# wifi.net
KiCad netlist of a schematic drawn in EAGLE
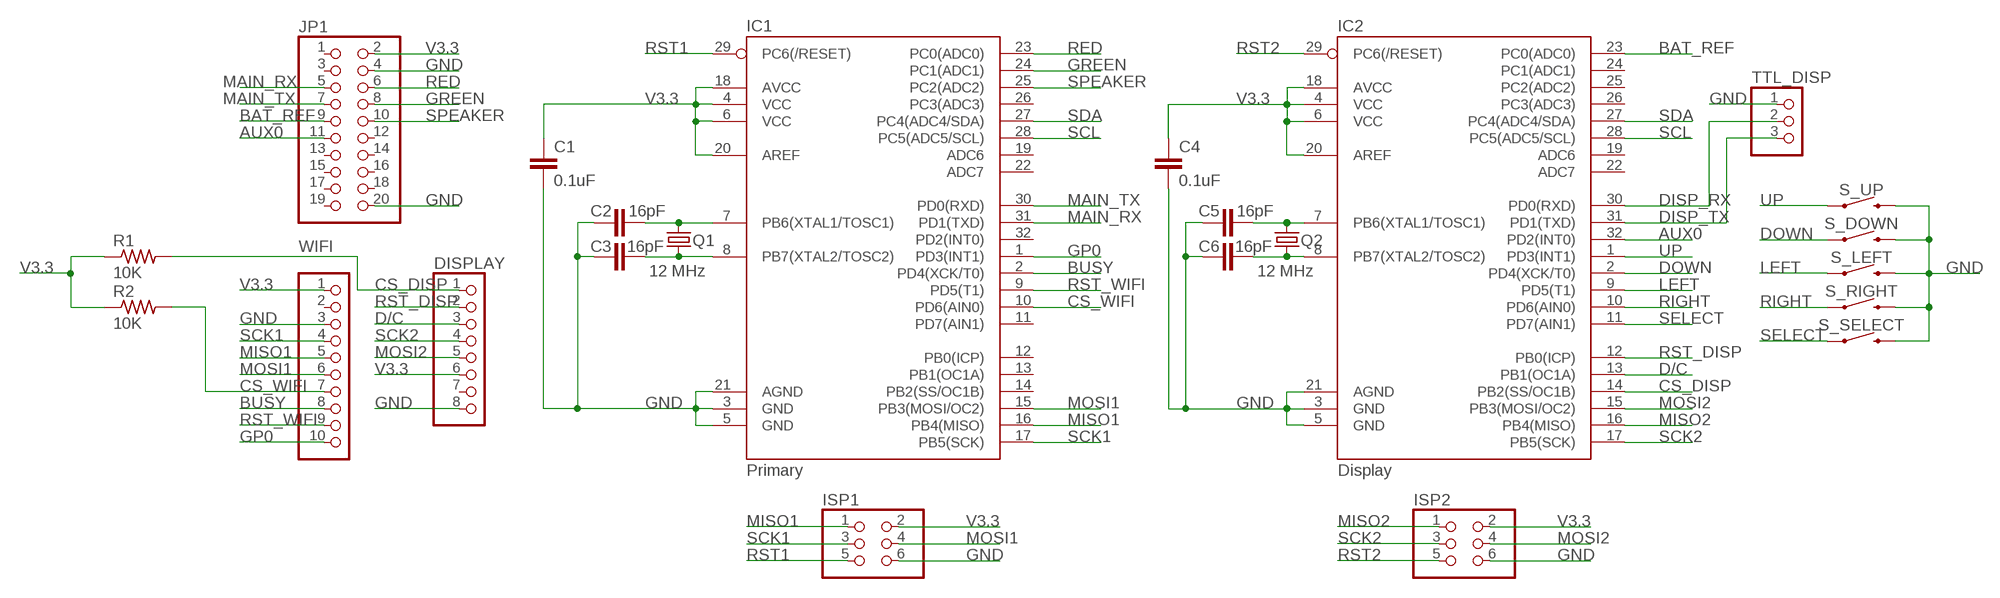
[diagram p0: schematic, sheet 1]

(export (version "E")
  (design (tool "Eeschema 10.0.6"))
  (components
    (comp (ref "C1")
      (value "0.1uF")
      (footprint "eagle-import:C1206")
      (libsource (lib "eagle-import") (part "C-EUC1206"))
    )
    (comp (ref "C2")
      (value "16pF")
      (footprint "eagle-import:C1206")
      (libsource (lib "eagle-import") (part "C-EUC1206"))
    )
    (comp (ref "C3")
      (value "16pF")
      (footprint "eagle-import:C1206")
      (libsource (lib "eagle-import") (part "C-EUC1206"))
    )
    (comp (ref "C4")
      (value "0.1uF")
      (footprint "eagle-import:C1206")
      (libsource (lib "eagle-import") (part "C-EUC1206"))
    )
    (comp (ref "C5")
      (value "16pF")
      (footprint "eagle-import:C1206")
      (libsource (lib "eagle-import") (part "C-EUC1206"))
    )
    (comp (ref "C6")
      (value "16pF")
      (footprint "eagle-import:C1206")
      (libsource (lib "eagle-import") (part "C-EUC1206"))
    )
    (comp (ref "DISPLAY")
      (value "PINHD-1X8CLEANBIG")
      (footprint "eagle-import:1X08-CLEANBIG")
      (libsource (lib "eagle-import") (part "PINHD-1X8CLEANBIG"))
    )
    (comp (ref "IC1")
      (value "Primary")
      (footprint "eagle-import:TQFP32-08")
      (libsource (lib "eagle-import") (part "ATMEGA328P_TQFP"))
    )
    (comp (ref "IC2")
      (value "Display")
      (footprint "eagle-import:TQFP32-08")
      (libsource (lib "eagle-import") (part "ATMEGA328P_TQFP"))
    )
    (comp (ref "ISP1")
      (value "PINHD-2X3")
      (footprint "eagle-import:2X03")
      (libsource (lib "eagle-import") (part "PINHD-2X3"))
    )
    (comp (ref "ISP2")
      (value "PINHD-2X3")
      (footprint "eagle-import:2X03")
      (libsource (lib "eagle-import") (part "PINHD-2X3"))
    )
    (comp (ref "JP1")
      (value "PINHD-2X10")
      (footprint "eagle-import:2X10")
      (libsource (lib "eagle-import") (part "PINHD-2X10"))
    )
    (comp (ref "Q1")
      (value "12 MHz")
      (footprint "eagle-import:HC49_S")
      (libsource (lib "eagle-import") (part "CRYSTALHC49S"))
    )
    (comp (ref "Q2")
      (value "12 MHz")
      (footprint "eagle-import:HC49_S")
      (libsource (lib "eagle-import") (part "CRYSTALHC49S"))
    )
    (comp (ref "R1")
      (value "10K")
      (footprint "eagle-import:R1206")
      (libsource (lib "eagle-import") (part "R-US_R1206"))
    )
    (comp (ref "R2")
      (value "10K")
      (footprint "eagle-import:R1206")
      (libsource (lib "eagle-import") (part "R-US_R1206"))
    )
    (comp (ref "S_DOWN")
      (value "MOMENTARY-SWITCH-SPST-PTH-6.0MM")
      (footprint "eagle-import:TACTILE_SWITCH_PTH_6.0MM")
      (libsource (lib "eagle-import") (part "MOMENTARY-SWITCH-SPST-PTH-6.0MM"))
    )
    (comp (ref "S_LEFT")
      (value "MOMENTARY-SWITCH-SPST-PTH-6.0MM")
      (footprint "eagle-import:TACTILE_SWITCH_PTH_6.0MM")
      (libsource (lib "eagle-import") (part "MOMENTARY-SWITCH-SPST-PTH-6.0MM"))
    )
    (comp (ref "S_RIGHT")
      (value "MOMENTARY-SWITCH-SPST-PTH-6.0MM")
      (footprint "eagle-import:TACTILE_SWITCH_PTH_6.0MM")
      (libsource (lib "eagle-import") (part "MOMENTARY-SWITCH-SPST-PTH-6.0MM"))
    )
    (comp (ref "S_SELECT")
      (value "MOMENTARY-SWITCH-SPST-PTH-6.0MM")
      (footprint "eagle-import:TACTILE_SWITCH_PTH_6.0MM")
      (libsource (lib "eagle-import") (part "MOMENTARY-SWITCH-SPST-PTH-6.0MM"))
    )
    (comp (ref "S_UP")
      (value "MOMENTARY-SWITCH-SPST-PTH-6.0MM")
      (footprint "eagle-import:TACTILE_SWITCH_PTH_6.0MM")
      (libsource (lib "eagle-import") (part "MOMENTARY-SWITCH-SPST-PTH-6.0MM"))
    )
    (comp (ref "TTL_DISP")
      (value "PINHD-1X3")
      (footprint "eagle-import:1X03")
      (libsource (lib "eagle-import") (part "PINHD-1X3"))
    )
    (comp (ref "WIFI")
      (value "PINHD-1X10")
      (footprint "eagle-import:1X10-BIG")
      (libsource (lib "eagle-import") (part "PINHD-1X10"))
    )
  )
  (nets
    (net (code "1") (name "/AUX0") (class "Default")
      (node (ref "IC2") (pin "32") (pinfunction "PD2(INT0)_32") (pintype "bidirectional"))
      (node (ref "JP1") (pin "11") (pinfunction "11_11") (pintype "passive"))
    )
    (net (code "2") (name "/BAT_REF") (class "Default")
      (node (ref "IC2") (pin "23") (pinfunction "PC0(ADC0)_23") (pintype "bidirectional"))
      (node (ref "JP1") (pin "9") (pinfunction "9_9") (pintype "passive"))
    )
    (net (code "3") (name "/BUSY") (class "Default")
      (node (ref "IC1") (pin "2") (pinfunction "PD4(XCK/T0)_2") (pintype "bidirectional"))
      (node (ref "WIFI") (pin "8") (pinfunction "8_8") (pintype "passive"))
    )
    (net (code "4") (name "/CS_DISP") (class "Default")
      (node (ref "DISPLAY") (pin "1") (pinfunction "1_1") (pintype "passive"))
      (node (ref "IC2") (pin "14") (pinfunction "PB2(SS/OC1B)_14") (pintype "bidirectional"))
      (node (ref "R1") (pin "2") (pinfunction "2_2") (pintype "passive"))
    )
    (net (code "5") (name "/CS_WIFI") (class "Default")
      (node (ref "IC1") (pin "10") (pinfunction "PD6(AIN0)_10") (pintype "bidirectional"))
      (node (ref "R2") (pin "2") (pinfunction "2_2") (pintype "passive"))
      (node (ref "WIFI") (pin "7") (pinfunction "7_7") (pintype "passive"))
    )
    (net (code "6") (name "/DISP_RX") (class "Default")
      (node (ref "IC2") (pin "30") (pinfunction "PD0(RXD)_30") (pintype "bidirectional"))
      (node (ref "TTL_DISP") (pin "2") (pinfunction "2_2") (pintype "passive"))
    )
    (net (code "7") (name "/DISP_TX") (class "Default")
      (node (ref "IC2") (pin "31") (pinfunction "PD1(TXD)_31") (pintype "bidirectional"))
      (node (ref "TTL_DISP") (pin "3") (pinfunction "3_3") (pintype "passive"))
    )
    (net (code "8") (name "/DOWN") (class "Default")
      (node (ref "IC2") (pin "2") (pinfunction "PD4(XCK/T0)_2") (pintype "bidirectional"))
      (node (ref "S_DOWN") (pin "1") (pinfunction "1_1") (pintype "passive"))
    )
    (net (code "9") (name "/D{slash}C") (class "Default")
      (node (ref "DISPLAY") (pin "3") (pinfunction "3_3") (pintype "passive"))
      (node (ref "IC2") (pin "13") (pinfunction "PB1(OC1A)_13") (pintype "bidirectional"))
    )
    (net (code "10") (name "/GND") (class "Default")
      (node (ref "C1") (pin "2") (pinfunction "2_2") (pintype "passive"))
      (node (ref "C2") (pin "1") (pinfunction "1_1") (pintype "passive"))
      (node (ref "C3") (pin "1") (pinfunction "1_1") (pintype "passive"))
      (node (ref "C4") (pin "2") (pinfunction "2_2") (pintype "passive"))
      (node (ref "C5") (pin "1") (pinfunction "1_1") (pintype "passive"))
      (node (ref "C6") (pin "1") (pinfunction "1_1") (pintype "passive"))
      (node (ref "DISPLAY") (pin "8") (pinfunction "8_8") (pintype "passive"))
      (node (ref "IC1") (pin "21") (pinfunction "AGND_21") (pintype "bidirectional"))
      (node (ref "IC1") (pin "3") (pinfunction "GND_3") (pintype "bidirectional"))
      (node (ref "IC1") (pin "5") (pinfunction "GND_5") (pintype "bidirectional"))
      (node (ref "IC2") (pin "21") (pinfunction "AGND_21") (pintype "bidirectional"))
      (node (ref "IC2") (pin "3") (pinfunction "GND_3") (pintype "bidirectional"))
      (node (ref "IC2") (pin "5") (pinfunction "GND_5") (pintype "bidirectional"))
      (node (ref "ISP1") (pin "6") (pinfunction "6_6") (pintype "passive"))
      (node (ref "ISP2") (pin "6") (pinfunction "6_6") (pintype "passive"))
      (node (ref "JP1") (pin "20") (pinfunction "20_20") (pintype "passive"))
      (node (ref "JP1") (pin "4") (pinfunction "4_4") (pintype "passive"))
      (node (ref "S_DOWN") (pin "3") (pinfunction "2_3") (pintype "passive"))
      (node (ref "S_LEFT") (pin "3") (pinfunction "2_3") (pintype "passive"))
      (node (ref "S_RIGHT") (pin "3") (pinfunction "2_3") (pintype "passive"))
      (node (ref "S_SELECT") (pin "3") (pinfunction "2_3") (pintype "passive"))
      (node (ref "S_UP") (pin "3") (pinfunction "2_3") (pintype "passive"))
      (node (ref "TTL_DISP") (pin "1") (pinfunction "1_1") (pintype "passive"))
      (node (ref "WIFI") (pin "3") (pinfunction "3_3") (pintype "passive"))
    )
    (net (code "11") (name "/GP0") (class "Default")
      (node (ref "IC1") (pin "1") (pinfunction "PD3(INT1)_1") (pintype "bidirectional"))
      (node (ref "WIFI") (pin "10") (pinfunction "10_10") (pintype "passive"))
    )
    (net (code "12") (name "/GREEN") (class "Default")
      (node (ref "IC1") (pin "24") (pinfunction "PC1(ADC1)_24") (pintype "bidirectional"))
      (node (ref "JP1") (pin "8") (pinfunction "8_8") (pintype "passive"))
    )
    (net (code "13") (name "/LEFT") (class "Default")
      (node (ref "IC2") (pin "9") (pinfunction "PD5(T1)_9") (pintype "bidirectional"))
      (node (ref "S_LEFT") (pin "1") (pinfunction "1_1") (pintype "passive"))
    )
    (net (code "14") (name "/MAIN_RX") (class "Default")
      (node (ref "IC1") (pin "31") (pinfunction "PD1(TXD)_31") (pintype "bidirectional"))
      (node (ref "JP1") (pin "5") (pinfunction "5_5") (pintype "passive"))
    )
    (net (code "15") (name "/MAIN_TX") (class "Default")
      (node (ref "IC1") (pin "30") (pinfunction "PD0(RXD)_30") (pintype "bidirectional"))
      (node (ref "JP1") (pin "7") (pinfunction "7_7") (pintype "passive"))
    )
    (net (code "16") (name "/MISO1") (class "Default")
      (node (ref "IC1") (pin "16") (pinfunction "PB4(MISO)_16") (pintype "bidirectional"))
      (node (ref "ISP1") (pin "1") (pinfunction "1_1") (pintype "passive"))
      (node (ref "WIFI") (pin "5") (pinfunction "5_5") (pintype "passive"))
    )
    (net (code "17") (name "/MISO2") (class "Default")
      (node (ref "IC2") (pin "16") (pinfunction "PB4(MISO)_16") (pintype "bidirectional"))
      (node (ref "ISP2") (pin "1") (pinfunction "1_1") (pintype "passive"))
    )
    (net (code "18") (name "/MOSI1") (class "Default")
      (node (ref "IC1") (pin "15") (pinfunction "PB3(MOSI/OC2)_15") (pintype "bidirectional"))
      (node (ref "ISP1") (pin "4") (pinfunction "4_4") (pintype "passive"))
      (node (ref "WIFI") (pin "6") (pinfunction "6_6") (pintype "passive"))
    )
    (net (code "19") (name "/MOSI2") (class "Default")
      (node (ref "DISPLAY") (pin "5") (pinfunction "5_5") (pintype "passive"))
      (node (ref "IC2") (pin "15") (pinfunction "PB3(MOSI/OC2)_15") (pintype "bidirectional"))
      (node (ref "ISP2") (pin "4") (pinfunction "4_4") (pintype "passive"))
    )
    (net (code "20") (name "/RED") (class "Default")
      (node (ref "IC1") (pin "23") (pinfunction "PC0(ADC0)_23") (pintype "bidirectional"))
      (node (ref "JP1") (pin "6") (pinfunction "6_6") (pintype "passive"))
    )
    (net (code "21") (name "/RIGHT") (class "Default")
      (node (ref "IC2") (pin "10") (pinfunction "PD6(AIN0)_10") (pintype "bidirectional"))
      (node (ref "S_RIGHT") (pin "1") (pinfunction "1_1") (pintype "passive"))
    )
    (net (code "22") (name "/RST1") (class "Default")
      (node (ref "IC1") (pin "29") (pinfunction "PC6(/RESET)_29") (pintype "bidirectional"))
      (node (ref "ISP1") (pin "5") (pinfunction "5_5") (pintype "passive"))
    )
    (net (code "23") (name "/RST2") (class "Default")
      (node (ref "IC2") (pin "29") (pinfunction "PC6(/RESET)_29") (pintype "bidirectional"))
      (node (ref "ISP2") (pin "5") (pinfunction "5_5") (pintype "passive"))
    )
    (net (code "24") (name "/RST_DISP") (class "Default")
      (node (ref "DISPLAY") (pin "2") (pinfunction "2_2") (pintype "passive"))
      (node (ref "IC2") (pin "12") (pinfunction "PB0(ICP)_12") (pintype "bidirectional"))
    )
    (net (code "25") (name "/RST_WIFI") (class "Default")
      (node (ref "IC1") (pin "9") (pinfunction "PD5(T1)_9") (pintype "bidirectional"))
      (node (ref "WIFI") (pin "9") (pinfunction "9_9") (pintype "passive"))
    )
    (net (code "26") (name "/SCK1") (class "Default")
      (node (ref "IC1") (pin "17") (pinfunction "PB5(SCK)_17") (pintype "bidirectional"))
      (node (ref "ISP1") (pin "3") (pinfunction "3_3") (pintype "passive"))
      (node (ref "WIFI") (pin "4") (pinfunction "4_4") (pintype "passive"))
    )
    (net (code "27") (name "/SCK2") (class "Default")
      (node (ref "DISPLAY") (pin "4") (pinfunction "4_4") (pintype "passive"))
      (node (ref "IC2") (pin "17") (pinfunction "PB5(SCK)_17") (pintype "bidirectional"))
      (node (ref "ISP2") (pin "3") (pinfunction "3_3") (pintype "passive"))
    )
    (net (code "28") (name "/SCL") (class "Default")
      (node (ref "IC1") (pin "28") (pinfunction "PC5(ADC5/SCL)_28") (pintype "bidirectional"))
      (node (ref "IC2") (pin "28") (pinfunction "PC5(ADC5/SCL)_28") (pintype "bidirectional"))
    )
    (net (code "29") (name "/SDA") (class "Default")
      (node (ref "IC1") (pin "27") (pinfunction "PC4(ADC4/SDA)_27") (pintype "bidirectional"))
      (node (ref "IC2") (pin "27") (pinfunction "PC4(ADC4/SDA)_27") (pintype "bidirectional"))
    )
    (net (code "30") (name "/SELECT") (class "Default")
      (node (ref "IC2") (pin "11") (pinfunction "PD7(AIN1)_11") (pintype "bidirectional"))
      (node (ref "S_SELECT") (pin "1") (pinfunction "1_1") (pintype "passive"))
    )
    (net (code "31") (name "/SPEAKER") (class "Default")
      (node (ref "IC1") (pin "25") (pinfunction "PC2(ADC2)_25") (pintype "bidirectional"))
      (node (ref "JP1") (pin "10") (pinfunction "10_10") (pintype "passive"))
    )
    (net (code "32") (name "/UP") (class "Default")
      (node (ref "IC2") (pin "1") (pinfunction "PD3(INT1)_1") (pintype "bidirectional"))
      (node (ref "S_UP") (pin "1") (pinfunction "1_1") (pintype "passive"))
    )
    (net (code "33") (name "/V3.3") (class "Default")
      (node (ref "C1") (pin "1") (pinfunction "1_1") (pintype "passive"))
      (node (ref "C4") (pin "1") (pinfunction "1_1") (pintype "passive"))
      (node (ref "DISPLAY") (pin "6") (pinfunction "6_6") (pintype "passive"))
      (node (ref "IC1") (pin "18") (pinfunction "AVCC_18") (pintype "bidirectional"))
      (node (ref "IC1") (pin "20") (pinfunction "AREF_20") (pintype "bidirectional"))
      (node (ref "IC1") (pin "4") (pinfunction "VCC_4") (pintype "bidirectional"))
      (node (ref "IC1") (pin "6") (pinfunction "VCC_6") (pintype "bidirectional"))
      (node (ref "IC2") (pin "18") (pinfunction "AVCC_18") (pintype "bidirectional"))
      (node (ref "IC2") (pin "20") (pinfunction "AREF_20") (pintype "bidirectional"))
      (node (ref "IC2") (pin "4") (pinfunction "VCC_4") (pintype "bidirectional"))
      (node (ref "IC2") (pin "6") (pinfunction "VCC_6") (pintype "bidirectional"))
      (node (ref "ISP1") (pin "2") (pinfunction "2_2") (pintype "passive"))
      (node (ref "ISP2") (pin "2") (pinfunction "2_2") (pintype "passive"))
      (node (ref "JP1") (pin "2") (pinfunction "2_2") (pintype "passive"))
      (node (ref "R1") (pin "1") (pinfunction "1_1") (pintype "passive"))
      (node (ref "R2") (pin "1") (pinfunction "1_1") (pintype "passive"))
      (node (ref "WIFI") (pin "1") (pinfunction "1_1") (pintype "passive"))
    )
    (net (code "34") (name "Net-(IC1-PB6(XTAL1{slash}TOSC1))") (class "Default")
      (node (ref "C2") (pin "2") (pinfunction "2_2") (pintype "passive"))
      (node (ref "IC1") (pin "7") (pinfunction "PB6(XTAL1/TOSC1)_7") (pintype "bidirectional"))
      (node (ref "Q1") (pin "2") (pinfunction "2_2") (pintype "passive"))
    )
    (net (code "35") (name "Net-(IC1-PB7(XTAL2{slash}TOSC2))") (class "Default")
      (node (ref "C3") (pin "2") (pinfunction "2_2") (pintype "passive"))
      (node (ref "IC1") (pin "8") (pinfunction "PB7(XTAL2/TOSC2)_8") (pintype "bidirectional"))
      (node (ref "Q1") (pin "1") (pinfunction "1_1") (pintype "passive"))
    )
    (net (code "36") (name "Net-(IC2-PB6(XTAL1{slash}TOSC1))") (class "Default")
      (node (ref "C5") (pin "2") (pinfunction "2_2") (pintype "passive"))
      (node (ref "IC2") (pin "7") (pinfunction "PB6(XTAL1/TOSC1)_7") (pintype "bidirectional"))
      (node (ref "Q2") (pin "2") (pinfunction "2_2") (pintype "passive"))
    )
    (net (code "37") (name "Net-(IC2-PB7(XTAL2{slash}TOSC2))") (class "Default")
      (node (ref "C6") (pin "2") (pinfunction "2_2") (pintype "passive"))
      (node (ref "IC2") (pin "8") (pinfunction "PB7(XTAL2/TOSC2)_8") (pintype "bidirectional"))
      (node (ref "Q2") (pin "1") (pinfunction "1_1") (pintype "passive"))
    )
    (net (code "38") (name "unconnected-(DISPLAY-Pad7)") (class "Default")
      (node (ref "DISPLAY") (pin "7") (pinfunction "7_7") (pintype "passive"))
    )
    (net (code "39") (name "unconnected-(IC1-ADC6-Pad19)") (class "Default")
      (node (ref "IC1") (pin "19") (pinfunction "ADC6_19") (pintype "bidirectional"))
    )
    (net (code "40") (name "unconnected-(IC1-ADC7-Pad22)") (class "Default")
      (node (ref "IC1") (pin "22") (pinfunction "ADC7_22") (pintype "bidirectional"))
    )
    (net (code "41") (name "unconnected-(IC1-PB0(ICP)-Pad12)") (class "Default")
      (node (ref "IC1") (pin "12") (pinfunction "PB0(ICP)_12") (pintype "bidirectional"))
    )
    (net (code "42") (name "unconnected-(IC1-PB1(OC1A)-Pad13)") (class "Default")
      (node (ref "IC1") (pin "13") (pinfunction "PB1(OC1A)_13") (pintype "bidirectional"))
    )
    (net (code "43") (name "unconnected-(IC1-PB2(SS{slash}OC1B)-Pad14)") (class "Default")
      (node (ref "IC1") (pin "14") (pinfunction "PB2(SS/OC1B)_14") (pintype "bidirectional"))
    )
    (net (code "44") (name "unconnected-(IC1-PC3(ADC3)-Pad26)") (class "Default")
      (node (ref "IC1") (pin "26") (pinfunction "PC3(ADC3)_26") (pintype "bidirectional"))
    )
    (net (code "45") (name "unconnected-(IC1-PD2(INT0)-Pad32)") (class "Default")
      (node (ref "IC1") (pin "32") (pinfunction "PD2(INT0)_32") (pintype "bidirectional"))
    )
    (net (code "46") (name "unconnected-(IC1-PD7(AIN1)-Pad11)") (class "Default")
      (node (ref "IC1") (pin "11") (pinfunction "PD7(AIN1)_11") (pintype "bidirectional"))
    )
    (net (code "47") (name "unconnected-(IC2-ADC6-Pad19)") (class "Default")
      (node (ref "IC2") (pin "19") (pinfunction "ADC6_19") (pintype "bidirectional"))
    )
    (net (code "48") (name "unconnected-(IC2-ADC7-Pad22)") (class "Default")
      (node (ref "IC2") (pin "22") (pinfunction "ADC7_22") (pintype "bidirectional"))
    )
    (net (code "49") (name "unconnected-(IC2-PC1(ADC1)-Pad24)") (class "Default")
      (node (ref "IC2") (pin "24") (pinfunction "PC1(ADC1)_24") (pintype "bidirectional"))
    )
    (net (code "50") (name "unconnected-(IC2-PC2(ADC2)-Pad25)") (class "Default")
      (node (ref "IC2") (pin "25") (pinfunction "PC2(ADC2)_25") (pintype "bidirectional"))
    )
    (net (code "51") (name "unconnected-(IC2-PC3(ADC3)-Pad26)") (class "Default")
      (node (ref "IC2") (pin "26") (pinfunction "PC3(ADC3)_26") (pintype "bidirectional"))
    )
    (net (code "52") (name "unconnected-(JP1-Pad1)") (class "Default")
      (node (ref "JP1") (pin "1") (pinfunction "1_1") (pintype "passive"))
    )
    (net (code "53") (name "unconnected-(JP1-Pad3)") (class "Default")
      (node (ref "JP1") (pin "3") (pinfunction "3_3") (pintype "passive"))
    )
    (net (code "54") (name "unconnected-(JP1-Pad12)") (class "Default")
      (node (ref "JP1") (pin "12") (pinfunction "12_12") (pintype "passive"))
    )
    (net (code "55") (name "unconnected-(JP1-Pad13)") (class "Default")
      (node (ref "JP1") (pin "13") (pinfunction "13_13") (pintype "passive"))
    )
    (net (code "56") (name "unconnected-(JP1-Pad14)") (class "Default")
      (node (ref "JP1") (pin "14") (pinfunction "14_14") (pintype "passive"))
    )
    (net (code "57") (name "unconnected-(JP1-Pad15)") (class "Default")
      (node (ref "JP1") (pin "15") (pinfunction "15_15") (pintype "passive"))
    )
    (net (code "58") (name "unconnected-(JP1-Pad16)") (class "Default")
      (node (ref "JP1") (pin "16") (pinfunction "16_16") (pintype "passive"))
    )
    (net (code "59") (name "unconnected-(JP1-Pad17)") (class "Default")
      (node (ref "JP1") (pin "17") (pinfunction "17_17") (pintype "passive"))
    )
    (net (code "60") (name "unconnected-(JP1-Pad18)") (class "Default")
      (node (ref "JP1") (pin "18") (pinfunction "18_18") (pintype "passive"))
    )
    (net (code "61") (name "unconnected-(JP1-Pad19)") (class "Default")
      (node (ref "JP1") (pin "19") (pinfunction "19_19") (pintype "passive"))
    )
    (net (code "62") (name "unconnected-(WIFI-Pad2)") (class "Default")
      (node (ref "WIFI") (pin "2") (pinfunction "2_2") (pintype "passive"))
    )
  )
)
